# LTM8074neg_PA.net
KiCad netlist of a schematic drawn in Altium Designer
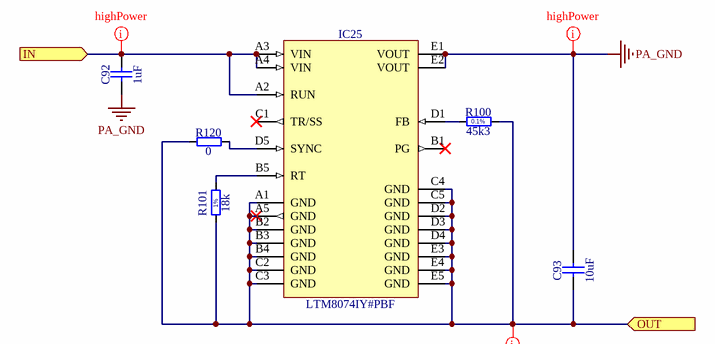
[diagram p0: LTM8074neg_PA.SchDoc]

(export (version "E")
  (design (tool "Eeschema 10.0.6"))
  (components
    (comp (ref "C92")
      (value "1uF")
      (footprint "CAPC2012X110N")
      (description "Non-polarised capacitor")
      (fields
        (field (name "PART NUMBER") "CC0805_1UF_50V_10%_X7R")
        (field (name "VOLTAGE") "50V")
        (field (name "AUTHOR") "CERN DEM JLC")
      )
      (libsource (lib "Capacitors") (part "Capacitor - non polarized"))
    )
    (comp (ref "C93")
      (value "10uF")
      (footprint "CAPC2012X95N")
      (description "Non-polarised capacitor")
      (fields
        (field (name "PART NUMBER") "CC0805_10UF_25V_10%_X5R")
        (field (name "VOLTAGE") "25V")
        (field (name "AUTHOR") "CERN DEM JLC")
      )
      (libsource (lib "Capacitors") (part "Capacitor - non polarized"))
    )
    (comp (ref "IC25")
      (value "LTM8074IY#PBF")
      (footprint "BGA25C65P5X5_400X400X198")
      (description "40VIN, 1.2A Silent Switcher µModule Regulator")
      (fields (field (name "MANUFACTURER") "LINEAR TECHNOLOGY") (field (name "AUTHOR") "CERN DEM JLC"))
      (libsource (lib "ICs And Semiconductors") (part "LTM8074"))
    )
    (comp (ref "R100")
      (value "45k3")
      (footprint "RESC1608X55N")
      (description "Resistor - 0.1%")
      (fields
        (field (name "PART NUMBER") "R0603_45K3_0.1%_0.063W_10PPM")
        (field (name "POWER") "0.063W")
        (field (name "AUTHOR") "CERN DEM JLC")
      )
      (libsource (lib "Resistors") (part "Resistor - 0.1%"))
    )
    (comp (ref "R101")
      (value "18k")
      (footprint "RESC1608X55N")
      (description "Resistor - 1%")
      (fields
        (field (name "PART NUMBER") "R0603_18K_1%_0.1W_100PPM")
        (field (name "POWER") "0.1W")
        (field (name "AUTHOR") "CERN DEM JLC")
      )
      (libsource (lib "Resistors") (part "Resistor - 1%"))
    )
    (comp (ref "R120")
      (value "0")
      (footprint "RESC1608X55N")
      (description "Resistor")
      (fields
        (field (name "PART NUMBER") "R0603_0R_JUMPER")
        (field (name "MANUFACTURER") "GENERIC")
        (field (name "AUTHOR") "CERN DEM JLC")
      )
      (libsource (lib "Resistors") (part "Resistor"))
    )
  )
  (nets
    (net (code "1") (name "/IN") (class "Default")
      (node (ref "C92") (pin "2") (pinfunction "2_2") (pintype "passive"))
      (node (ref "IC25") (pin "A2") (pinfunction "RUN_A2") (pintype "input"))
      (node (ref "IC25") (pin "A3") (pinfunction "VIN_A3") (pintype "input"))
      (node (ref "IC25") (pin "A4") (pinfunction "VIN_A4") (pintype "input"))
    )
    (net (code "2") (name "/OUT") (class "Default")
      (node (ref "C93") (pin "1") (pinfunction "1_1") (pintype "passive"))
      (node (ref "IC25") (pin "A1") (pinfunction "GND_A1") (pintype "power_in"))
      (node (ref "IC25") (pin "A5") (pinfunction "GND_A5") (pintype "output"))
      (node (ref "IC25") (pin "B2") (pinfunction "GND_B2") (pintype "power_in"))
      (node (ref "IC25") (pin "B3") (pinfunction "GND_B3") (pintype "power_in"))
      (node (ref "IC25") (pin "B4") (pinfunction "GND_B4") (pintype "power_in"))
      (node (ref "IC25") (pin "C2") (pinfunction "GND_C2") (pintype "power_in"))
      (node (ref "IC25") (pin "C3") (pinfunction "GND_C3") (pintype "power_in"))
      (node (ref "IC25") (pin "C4") (pinfunction "GND_C4") (pintype "power_in"))
      (node (ref "IC25") (pin "C5") (pinfunction "GND_C5") (pintype "power_in"))
      (node (ref "IC25") (pin "D2") (pinfunction "GND_D2") (pintype "power_in"))
      (node (ref "IC25") (pin "D3") (pinfunction "GND_D3") (pintype "power_in"))
      (node (ref "IC25") (pin "D4") (pinfunction "GND_D4") (pintype "power_in"))
      (node (ref "IC25") (pin "E3") (pinfunction "GND_E3") (pintype "power_in"))
      (node (ref "IC25") (pin "E4") (pinfunction "GND_E4") (pintype "power_in"))
      (node (ref "IC25") (pin "E5") (pinfunction "GND_E5") (pintype "power_in"))
      (node (ref "R100") (pin "2") (pinfunction "2_2") (pintype "passive"))
      (node (ref "R101") (pin "1") (pinfunction "1_1") (pintype "passive"))
      (node (ref "R120") (pin "1") (pinfunction "1_1") (pintype "passive"))
    )
    (net (code "3") (name "Net-(IC25-FB)") (class "Default")
      (node (ref "IC25") (pin "D1") (pinfunction "FB_D1") (pintype "input"))
      (node (ref "R100") (pin "1") (pinfunction "1_1") (pintype "passive"))
    )
    (net (code "4") (name "Net-(IC25-RT)") (class "Default")
      (node (ref "IC25") (pin "B5") (pinfunction "RT_B5") (pintype "input"))
      (node (ref "R101") (pin "2") (pinfunction "2_2") (pintype "passive"))
    )
    (net (code "5") (name "Net-(IC25-SYNC)") (class "Default")
      (node (ref "IC25") (pin "D5") (pinfunction "SYNC_D5") (pintype "input"))
      (node (ref "R120") (pin "2") (pinfunction "2_2") (pintype "passive"))
    )
    (net (code "6") (name "PA_GND") (class "Default")
      (node (ref "C92") (pin "1") (pinfunction "1_1") (pintype "passive"))
      (node (ref "C93") (pin "2") (pinfunction "2_2") (pintype "passive"))
      (node (ref "IC25") (pin "E1") (pinfunction "VOUT_E1") (pintype "power_in"))
      (node (ref "IC25") (pin "E2") (pinfunction "VOUT_E2") (pintype "power_in"))
    )
    (net (code "7") (name "unconnected-(IC25-PG-PadB1)") (class "Default")
      (node (ref "IC25") (pin "B1") (pinfunction "PG_B1") (pintype "output+no_connect"))
    )
    (net (code "8") (name "unconnected-(IC25-TR{slash}SS-PadC1)") (class "Default")
      (node (ref "IC25") (pin "C1") (pinfunction "TR/SS_C1") (pintype "output+no_connect"))
    )
  )
)
